# POWER_SUPPLY.net
KiCad netlist of a schematic drawn in Altium Designer
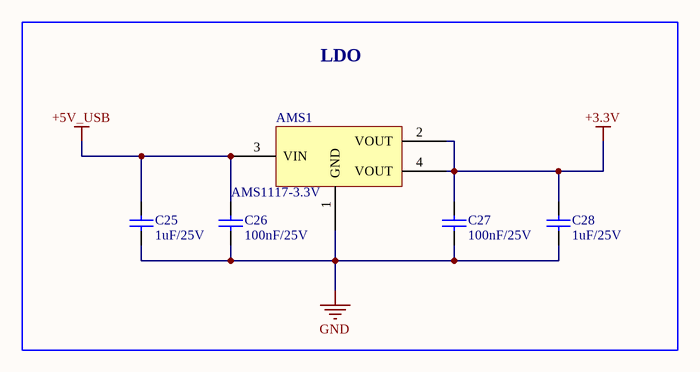
[diagram p0: POWER_SUPPLY.SchDoc]

(export (version "E")
  (design (tool "Eeschema 10.0.6"))
  (components
    (comp (ref "AMS1")
      (value "AMS1117-3.3V")
      (footprint "SOT223")
      (description "Dán")
      (libsource (lib "Altium_Lib_by_KhueNguyenCreator") (part "AMS1117 SMD"))
    )
    (comp (ref "C25")
      (value "1uF/25V")
      (footprint "CAP-SM-0805")
      (description "Capacitor")
      (fields (field (name "Comment") "Cap Non-Pol SMD"))
      (libsource (lib "PIF_Library") (part "Cap Non-Pol SMD"))
    )
    (comp (ref "C26")
      (value "100nF/25V")
      (footprint "CAP-SM-0805")
      (description "Capacitor")
      (fields (field (name "Comment") "Cap Non-Pol SMD"))
      (libsource (lib "PIF_Library") (part "Cap Non-Pol SMD"))
    )
    (comp (ref "C27")
      (value "100nF/25V")
      (footprint "CAP-SM-0805")
      (description "Capacitor")
      (fields (field (name "Comment") "Cap Non-Pol SMD"))
      (libsource (lib "PIF_Library") (part "Cap Non-Pol SMD"))
    )
    (comp (ref "C28")
      (value "1uF/25V")
      (footprint "CAP-SM-0805")
      (description "Capacitor")
      (fields (field (name "Comment") "Cap Non-Pol SMD"))
      (libsource (lib "PIF_Library") (part "Cap Non-Pol SMD"))
    )
  )
  (nets
    (net (code "1") (name "+3.3V") (class "Default")
      (node (ref "AMS1") (pin "2") (pinfunction "VOUT_2") (pintype "passive"))
      (node (ref "AMS1") (pin "4") (pinfunction "VOUT_4") (pintype "passive"))
      (node (ref "C27") (pin "2") (pinfunction "2_2") (pintype "passive"))
      (node (ref "C28") (pin "2") (pinfunction "2_2") (pintype "passive"))
    )
    (net (code "2") (name "+5V_USB") (class "Default")
      (node (ref "AMS1") (pin "3") (pinfunction "VIN_3") (pintype "passive"))
      (node (ref "C25") (pin "2") (pinfunction "2_2") (pintype "passive"))
      (node (ref "C26") (pin "2") (pinfunction "2_2") (pintype "passive"))
    )
    (net (code "3") (name "GND") (class "Default")
      (node (ref "AMS1") (pin "1") (pinfunction "GND_1") (pintype "passive"))
      (node (ref "C25") (pin "1") (pinfunction "1_1") (pintype "passive"))
      (node (ref "C26") (pin "1") (pinfunction "1_1") (pintype "passive"))
      (node (ref "C27") (pin "1") (pinfunction "1_1") (pintype "passive"))
      (node (ref "C28") (pin "1") (pinfunction "1_1") (pintype "passive"))
    )
  )
)
